# Sheet1.net
KiCad netlist of a schematic drawn in Altium Designer
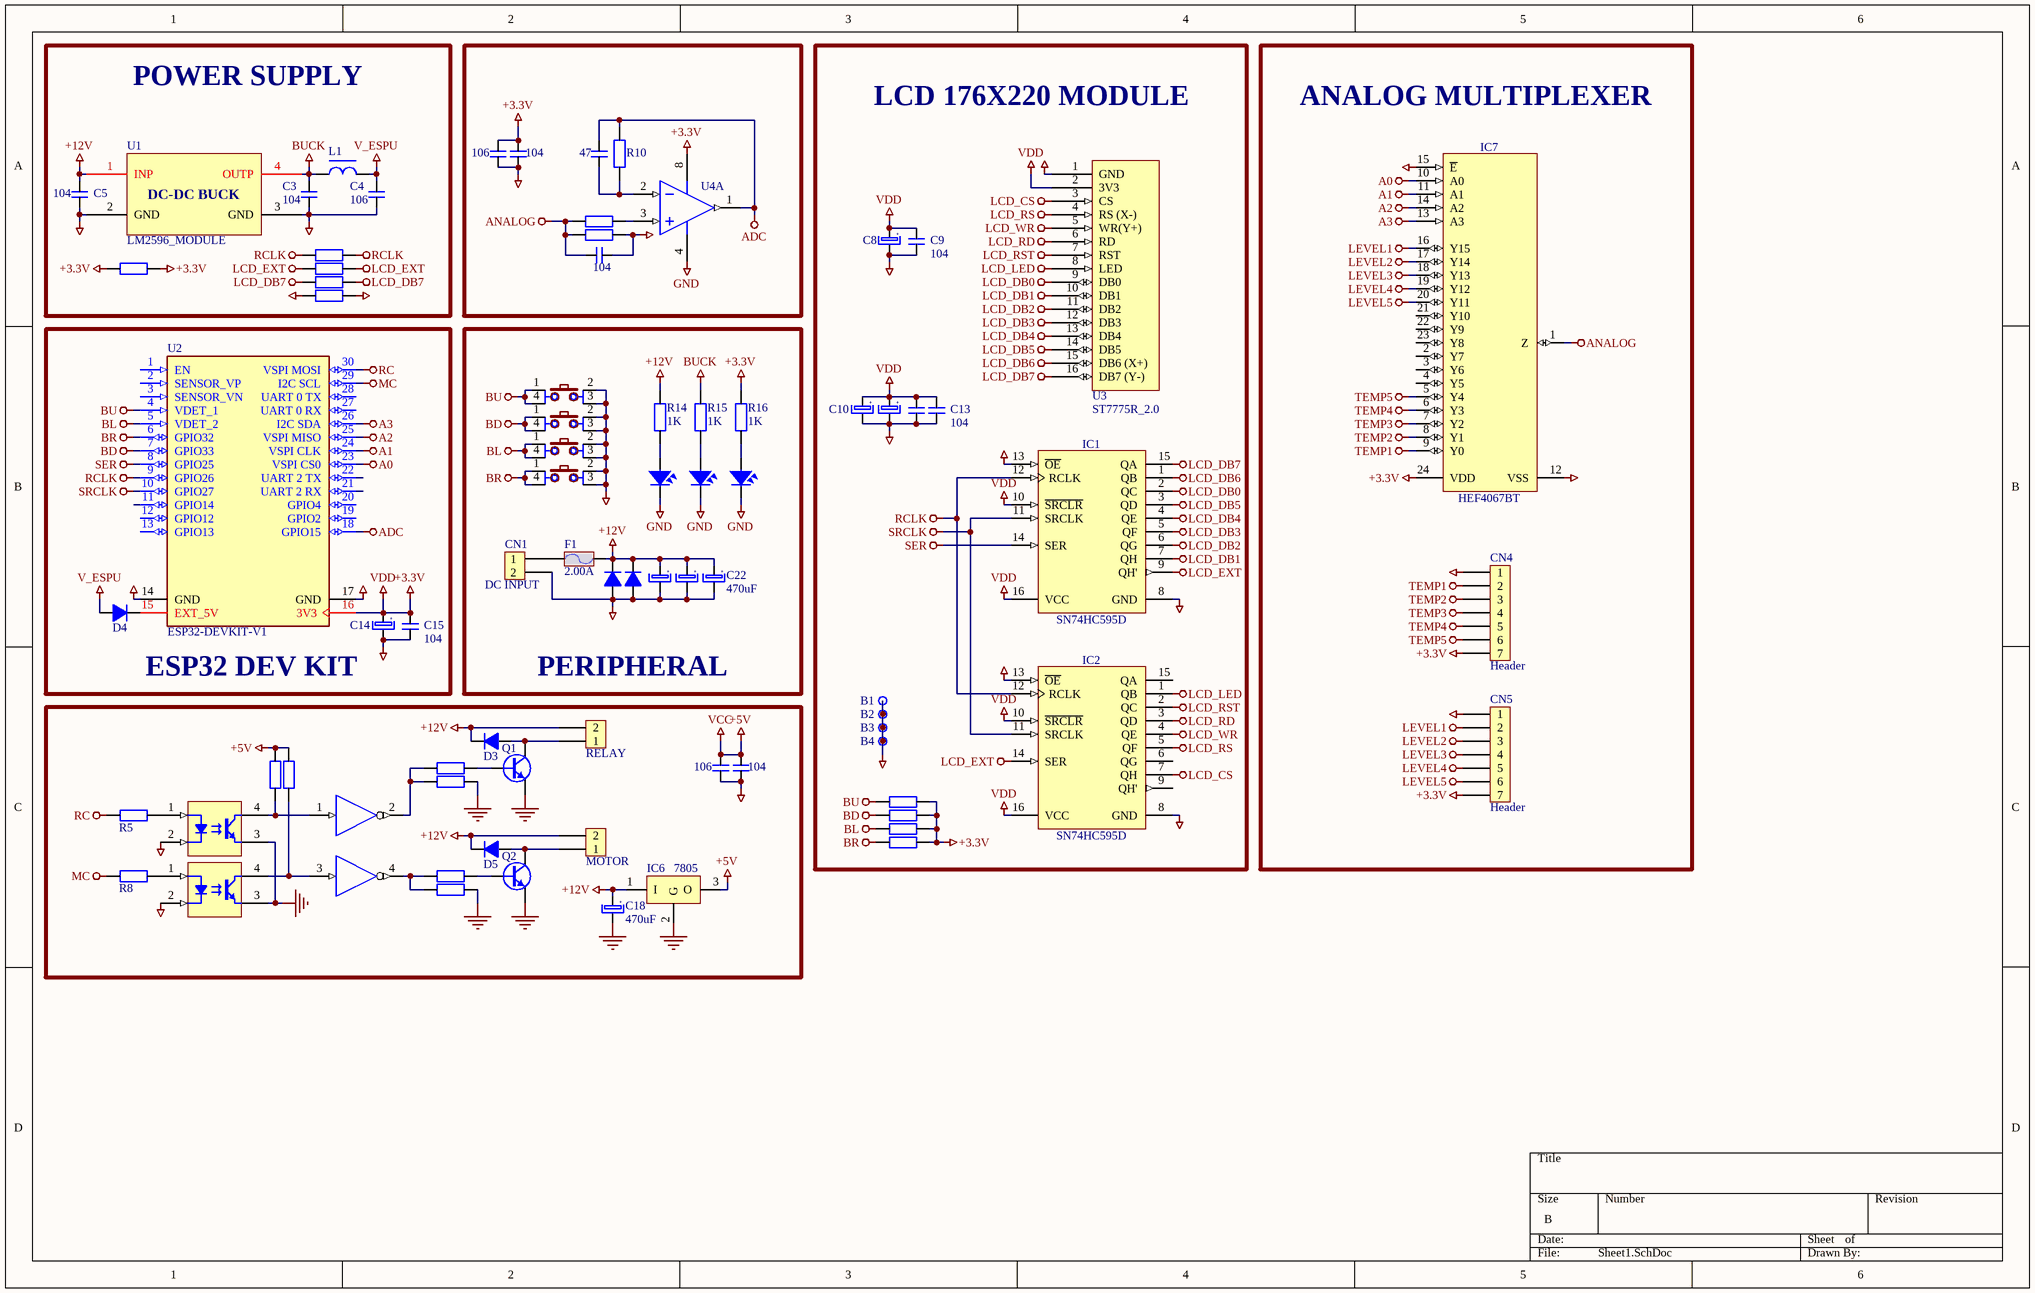
[diagram p0: Sheet1.SchDoc]

(export (version "E")
  (design (tool "Eeschema 10.0.6"))
  (components
    (comp (ref "B1")
      (value "Plated Hole")
      (footprint "MTG300_600")
      (description "Single Terminal Socket")
      (fields (field (name "PART NUMBER") "PLATED_HOLE3.0_PAD6.0") (field (name "AUTHOR") "CERN DEM JLC"))
      (libsource (lib "Eletro-mechanical") (part "Single Terminal Socket"))
    )
    (comp (ref "B2")
      (value "Plated Hole")
      (footprint "MTG300_600")
      (description "Single Terminal Socket")
      (fields (field (name "PART NUMBER") "PLATED_HOLE3.0_PAD6.0") (field (name "AUTHOR") "CERN DEM JLC"))
      (libsource (lib "Eletro-mechanical") (part "Single Terminal Socket"))
    )
    (comp (ref "B3")
      (value "Plated Hole")
      (footprint "MTG300_600")
      (description "Single Terminal Socket")
      (fields (field (name "PART NUMBER") "PLATED_HOLE3.0_PAD6.0") (field (name "AUTHOR") "CERN DEM JLC"))
      (libsource (lib "Eletro-mechanical") (part "Single Terminal Socket"))
    )
    (comp (ref "B4")
      (value "Plated Hole")
      (footprint "MTG300_600")
      (description "Single Terminal Socket")
      (fields (field (name "PART NUMBER") "PLATED_HOLE3.0_PAD6.0") (field (name "AUTHOR") "CERN DEM JLC"))
      (libsource (lib "Eletro-mechanical") (part "Single Terminal Socket"))
    )
    (comp (ref "C1")
      (value "106")
      (footprint "CAP-SMD-0805")
      (description "Non-polar capacitor")
      (libsource (lib "Library") (part "Cap-Non-SMD"))
    )
    (comp (ref "C2")
      (value "104")
      (footprint "CAP-SMD-0805")
      (description "Non-polar capacitor")
      (libsource (lib "Library") (part "Cap-Non-SMD"))
    )
    (comp (ref "C3")
      (value "104")
      (footprint "Cap-Non-150mil")
      (description "Non-polar capacitor")
      (libsource (lib "Library") (part "Cap-Non-Dip"))
    )
    (comp (ref "C4")
      (value "106")
      (footprint "CAP-SMD-0805")
      (description "Non-polar capacitor")
      (libsource (lib "Library") (part "Cap-Non-SMD"))
    )
    (comp (ref "C5")
      (value "104")
      (footprint "Cap-Non-150mil")
      (description "Non-polar capacitor")
      (libsource (lib "Library") (part "Cap-Non-Dip"))
    )
    (comp (ref "C6")
      (value "47")
      (footprint "CAP-SMD-0805")
      (description "Non-polar capacitor")
      (libsource (lib "Library") (part "Cap-Non-SMD"))
    )
    (comp (ref "C7")
      (value "104")
      (footprint "CAP-SMD-0805")
      (description "Non-polar capacitor")
      (libsource (lib "Library") (part "Cap-Non-SMD"))
    )
    (comp (ref "C8")
      (value "220uF")
      (footprint "Cap-P-2.5/5")
      (description "Polarized capacitor")
      (libsource (lib "Library") (part "Cap-Pol-Dip"))
    )
    (comp (ref "C9")
      (value "104")
      (footprint "Cap-Non-150mil")
      (description "Non-polar capacitor")
      (libsource (lib "Library") (part "Cap-Non-Dip"))
    )
    (comp (ref "C10")
      (value "220uF")
      (footprint "Cap-P-2.5/5")
      (description "Polarized capacitor")
      (libsource (lib "Library") (part "Cap-Pol-Dip"))
    )
    (comp (ref "C11")
      (value "220uF")
      (footprint "Cap-P-2.5/5")
      (description "Polarized capacitor")
      (libsource (lib "Library") (part "Cap-Pol-Dip"))
    )
    (comp (ref "C12")
      (value "104")
      (footprint "Cap-Non-150mil")
      (description "Non-polar capacitor")
      (libsource (lib "Library") (part "Cap-Non-Dip"))
    )
    (comp (ref "C13")
      (value "104")
      (footprint "Cap-Non-150mil")
      (description "Non-polar capacitor")
      (libsource (lib "Library") (part "Cap-Non-Dip"))
    )
    (comp (ref "C14")
      (value "220uF")
      (footprint "Cap-P-2.5/5")
      (description "Polarized capacitor")
      (libsource (lib "Library") (part "Cap-Pol-Dip"))
    )
    (comp (ref "C15")
      (value "104")
      (footprint "Cap-Non-150mil")
      (description "Non-polar capacitor")
      (libsource (lib "Library") (part "Cap-Non-Dip"))
    )
    (comp (ref "C16")
      (value "106")
      (footprint "CAP-SMD-0805")
      (description "Non-polar capacitor")
      (libsource (lib "Library") (part "Cap-Non-SMD"))
    )
    (comp (ref "C17")
      (value "104")
      (footprint "CAP-SMD-0805")
      (description "Non-polar capacitor")
      (libsource (lib "Library") (part "Cap-Non-SMD"))
    )
    (comp (ref "C18")
      (value "470uF")
      (footprint "Cap-P-3.8/6.3")
      (description "Polarized capacitor")
      (libsource (lib "Library") (part "Cap-Pol-Dip"))
    )
    (comp (ref "C20")
      (value "470uF")
      (footprint "Cap-P-3.8/6.3")
      (description "Polarized capacitor")
      (libsource (lib "Library") (part "Cap-Pol-Dip"))
    )
    (comp (ref "C21")
      (value "470uF")
      (footprint "Cap-P-3.8/6.3")
      (description "Polarized capacitor")
      (libsource (lib "Library") (part "Cap-Pol-Dip"))
    )
    (comp (ref "C22")
      (value "470uF")
      (footprint "Cap-P-3.8/6.3")
      (description "Polarized capacitor")
      (libsource (lib "Library") (part "Cap-Pol-Dip"))
    )
    (comp (ref "CN1") (value "DC INPUT") (footprint "KF2/5.08") (libsource (lib "Library") (part "KF 2")))
    (comp (ref "CN2") (value "RELAY") (footprint "KF2/5.08") (libsource (lib "") (part "KF 2_1")))
    (comp (ref "CN3") (value "MOTOR") (footprint "KF2/5.08") (libsource (lib "") (part "KF 2_1")))
    (comp (ref "CN4") (value "Header") (footprint "Header 7P") (libsource (lib "Library") (part "Header 7")))
    (comp (ref "CN5") (value "Header") (footprint "Header 7P") (libsource (lib "Library") (part "Header 7")))
    (comp (ref "D1")
      (value "SS14")
      (footprint "SOD 106")
      (description "Diode SMD")
      (libsource (lib "Library") (part "Diode SMD"))
    )
    (comp (ref "D2")
      (value "SS14")
      (footprint "SOD 106")
      (description "Diode SMD")
      (libsource (lib "Library") (part "Diode SMD"))
    )
    (comp (ref "D3")
      (value "SS14")
      (footprint "SOD 106")
      (description "Diode SMD")
      (libsource (lib "Library") (part "Diode SMD"))
    )
    (comp (ref "D4")
      (value "SS14")
      (footprint "SOD 106")
      (description "Diode SMD")
      (libsource (lib "Library") (part "Diode SMD"))
    )
    (comp (ref "D5")
      (value "SS14")
      (footprint "SOD 106")
      (description "Diode SMD")
      (libsource (lib "Library") (part "Diode SMD"))
    )
    (comp (ref "F1") (value "2.00A") (footprint "Fuse-Dip1") (libsource (lib "Library") (part "Fuse Dip")))
    (comp (ref "IC1")
      (value "SN74HC595D")
      (footprint "SOIC127P600X175-16N")
      (description "8-Bit Shift Register With 3-State Output Register")
      (fields (field (name "MANUFACTURER") "TEXAS INSTRUMENTS") (field (name "AUTHOR") "CERN DEM JLC"))
      (libsource (lib "ICs And Semiconductors") (part "74595"))
    )
    (comp (ref "IC2")
      (value "SN74HC595D")
      (footprint "SOIC127P600X175-16N")
      (description "8-Bit Shift Register With 3-State Output Register")
      (fields (field (name "MANUFACTURER") "TEXAS INSTRUMENTS") (field (name "AUTHOR") "CERN DEM JLC"))
      (libsource (lib "ICs And Semiconductors") (part "74595"))
    )
    (comp (ref "IC3")
      (value "FOD817DSD")
      (footprint "DIP4")
      (description "Single Optocoupler")
      (fields (field (name "MANUFACTURER") "FAIRCHILD SEMICONDUCTOR") (field (name "AUTHOR") "CERN DEM JLC"))
      (libsource (lib "ICs And Semiconductors") (part "Optocoupler Type7"))
    )
    (comp (ref "IC4")
      (value "74HC14D")
      (footprint "SOIC127P600X175-14N")
      (description "Hex Schmitt-Trigger Inverter")
      (fields (field (name "MANUFACTURER") "NXP SEMICONDUCTORS") (field (name "AUTHOR") "CERN DEM JLC"))
      (libsource (lib "ICs And Semiconductors") (part "7414"))
    )
    (comp (ref "IC5")
      (value "FOD817DSD")
      (footprint "DIP4")
      (description "Single Optocoupler")
      (fields (field (name "MANUFACTURER") "FAIRCHILD SEMICONDUCTOR") (field (name "AUTHOR") "CERN DEM JLC"))
      (libsource (lib "ICs And Semiconductors") (part "Optocoupler Type7"))
    )
    (comp (ref "IC6")
      (value "7805")
      (footprint "TO252")
      (description "Power IC, 5V-1A")
      (libsource (lib "Library") (part "7805"))
    )
    (comp (ref "IC7")
      (value "HEF4067BT")
      (footprint "SOIC127P1032X265-24N")
      (description "16-Channel Analog Multiplexer/Demultiplexer")
      (fields (field (name "MANUFACTURER") "NXP SEMICONDUCTORS") (field (name "AUTHOR") "CERN DEM JLC"))
      (libsource (lib "ICs And Semiconductors") (part "4067"))
    )
    (comp (ref "L1")
      (value "470uH")
      (footprint "L-DIP-M-5.3")
      (description "Inductor")
      (libsource (lib "Library") (part "IND-DIP-1"))
    )
    (comp (ref "LED1") (value "POWER") (footprint "LED-0805") (libsource (lib "Library") (part "LED_SMD")))
    (comp (ref "LED2") (value "ESP-5.0V") (footprint "LED-0805") (libsource (lib "Library") (part "LED_SMD")))
    (comp (ref "LED3") (value "ESP-3.3V") (footprint "LED-0805") (libsource (lib "Library") (part "LED_SMD")))
    (comp (ref "Q1")
      (value "MJD122G")
      (footprint "TO228P991X239-3N-R552X520")
      (description "NPN Transistor")
      (fields
        (field (name "PART NUMBER") "MJD340G")
        (field (name "MANUFACTURER") "ON SEMICONDUCTOR")
        (field (name "AUTHOR") "CERN DEM JLC")
      )
      (libsource (lib "ICs And Semiconductors") (part "NPN B1 E2 C3"))
    )
    (comp (ref "Q2")
      (value "MJD122G")
      (footprint "TO228P991X239-3N-R552X520")
      (description "NPN Transistor")
      (fields
        (field (name "PART NUMBER") "MJD340G")
        (field (name "MANUFACTURER") "ON SEMICONDUCTOR")
        (field (name "AUTHOR") "CERN DEM JLC")
      )
      (libsource (lib "ICs And Semiconductors") (part "NPN B1 E2 C3"))
    )
    (comp (ref "R1")
      (value "1K")
      (footprint "RES-SMD-0805")
      (description "Resistor 1/4W")
      (libsource (lib "Library") (part "Res 1/4W"))
    )
    (comp (ref "R2")
      (value "1K")
      (footprint "RES-SMD-0805")
      (description "Resistor 1/4W")
      (libsource (lib "Library") (part "Res 1/4W"))
    )
    (comp (ref "R3")
      (value "1K")
      (footprint "RES-SMD-0805")
      (description "Resistor 1/4W")
      (libsource (lib "Library") (part "Res 1/4W"))
    )
    (comp (ref "R4")
      (value "10K")
      (footprint "RES-SMD-0805")
      (description "Resistor 1/4W")
      (libsource (lib "Library") (part "Res 1/4W"))
    )
    (comp (ref "R5")
      (value "1K")
      (footprint "RES-SMD-0805")
      (description "Resistor 1/4W")
      (libsource (lib "Library") (part "Res 1/4W"))
    )
    (comp (ref "R6")
      (value "1K")
      (footprint "RES-SMD-0805")
      (description "Resistor 1/4W")
      (libsource (lib "Library") (part "Res 1/4W"))
    )
    (comp (ref "R7")
      (value "10K")
      (footprint "RES-SMD-0805")
      (description "Resistor 1/4W")
      (libsource (lib "Library") (part "Res 1/4W"))
    )
    (comp (ref "R8")
      (value "1K")
      (footprint "RES-SMD-0805")
      (description "Resistor 1/4W")
      (libsource (lib "Library") (part "Res 1/4W"))
    )
    (comp (ref "R10")
      (value "10K")
      (footprint "RES-SMD-0805")
      (description "Resistor SMD")
      (libsource (lib "Library") (part "Res SMD"))
    )
    (comp (ref "R11")
      (value "10K")
      (footprint "RES-SMD-0805")
      (description "Resistor SMD")
      (libsource (lib "Library") (part "Res SMD"))
    )
    (comp (ref "R12")
      (value "1K")
      (footprint "RES-SMD-0805")
      (description "Resistor SMD")
      (libsource (lib "Library") (part "Res SMD"))
    )
    (comp (ref "R13")
      (value "1K")
      (footprint "RES-SMD-0805")
      (description "Resistor 1/4W")
      (libsource (lib "Library") (part "Res 1/4W"))
    )
    (comp (ref "R14")
      (value "1K")
      (footprint "RES-SMD-0805")
      (description "Resistor 1/4W")
      (libsource (lib "Library") (part "Res 1/4W"))
    )
    (comp (ref "R15")
      (value "1K")
      (footprint "RES-SMD-0805")
      (description "Resistor 1/4W")
      (libsource (lib "Library") (part "Res 1/4W"))
    )
    (comp (ref "R16")
      (value "1K")
      (footprint "RES-SMD-0805")
      (description "Resistor 1/4W")
      (libsource (lib "Library") (part "Res 1/4W"))
    )
    (comp (ref "R17")
      (value "0R")
      (footprint "RES-SMD-0805")
      (description "Resistor SMD")
      (libsource (lib "Library") (part "Res SMD"))
    )
    (comp (ref "R18")
      (value "0R")
      (footprint "RES-SMD-0805")
      (description "Resistor SMD")
      (libsource (lib "Library") (part "Res SMD"))
    )
    (comp (ref "R19")
      (value "0R")
      (footprint "RES-SMD-0805")
      (description "Resistor SMD")
      (libsource (lib "Library") (part "Res SMD"))
    )
    (comp (ref "R20")
      (value "0R")
      (footprint "RES-SMD-1206")
      (description "Resistor SMD")
      (libsource (lib "Library") (part "Res SMD"))
    )
    (comp (ref "R21")
      (value "1K")
      (footprint "RES-SMD-0805")
      (description "Resistor 1/4W")
      (libsource (lib "Library") (part "Res 1/4W"))
    )
    (comp (ref "R22")
      (value "1K")
      (footprint "RES-SMD-0805")
      (description "Resistor 1/4W")
      (libsource (lib "Library") (part "Res 1/4W"))
    )
    (comp (ref "R23")
      (value "1K")
      (footprint "RES-SMD-0805")
      (description "Resistor 1/4W")
      (libsource (lib "Library") (part "Res 1/4W"))
    )
    (comp (ref "R27")
      (value "0R")
      (footprint "RES-SMD-1206")
      (description "Resistor 1/4W")
      (libsource (lib "Library") (part "Res 1/4W"))
    )
    (comp (ref "SW1")
      (value "UP")
      (footprint "Button-Dip4/6x6")
      (description "Switch button 4 pin")
      (libsource (lib "Library") (part "Button-4"))
    )
    (comp (ref "SW2")
      (value "DOWN")
      (footprint "Button-Dip4/6x6")
      (description "Switch button 4 pin")
      (libsource (lib "Library") (part "Button-4"))
    )
    (comp (ref "SW3")
      (value "LEFT")
      (footprint "Button-Dip4/6x6")
      (description "Switch button 4 pin")
      (libsource (lib "Library") (part "Button-4"))
    )
    (comp (ref "SW4")
      (value "RIGHT")
      (footprint "Button-Dip4/6x6")
      (description "Switch button 4 pin")
      (libsource (lib "Library") (part "Button-4"))
    )
    (comp (ref "U1")
      (value "LM2596_MODULE")
      (footprint "LM2596_MODULE")
      (libsource (lib "TOAN_VERSION_1_0") (part "LM2596_MODULE"))
    )
    (comp (ref "U2")
      (value "ESP32-DEVKIT-V1")
      (footprint "MODULE_ESP32-DEVKITC-32D")
      (fields (field (name "MF") "Espressif Systems") (field (name "MP") "ESP32-DEVKITC-32D"))
      (libsource (lib "TOAN_VERSION_1_0") (part "ESP32-DEVKIT-V1"))
    )
    (comp (ref "U3")
      (value "ST7775R_2.0")
      (footprint "LCD_176X220_MODULE")
      (libsource (lib "TOAN_VERSION_1_0") (part "LCD_176x220_ST7775R"))
    )
    (comp (ref "U4")
      (value "LM6132")
      (footprint "SOIC-8S")
      (description "Dual Low Power 10 MHz Rail-to-Rail I/O Operational Amplifier, 8-pin Narrow SOIC")
      (fields
        (field (name "PARTNUMBER") "LM6132AIM")
        (field (name "MANUFACTURER") "National Semiconductor")
        (field (name "PUBLISHER") "Altium Limited")
      )
      (libsource (lib "NSC Amplifier") (part "LM6132AIM"))
    )
  )
  (nets
    (net (code "1") (name "+3.3V") (class "Default")
      (node (ref "C1") (pin "2") (pinfunction "2_2") (pintype "passive"))
      (node (ref "C10") (pin "1") (pinfunction "1_1") (pintype "passive"))
      (node (ref "C11") (pin "1") (pinfunction "1_1") (pintype "passive"))
      (node (ref "C12") (pin "2") (pinfunction "2_2") (pintype "passive"))
      (node (ref "C13") (pin "2") (pinfunction "2_2") (pintype "passive"))
      (node (ref "C14") (pin "1") (pinfunction "1_1") (pintype "passive"))
      (node (ref "C15") (pin "2") (pinfunction "2_2") (pintype "passive"))
      (node (ref "C2") (pin "2") (pinfunction "2_2") (pintype "passive"))
      (node (ref "C8") (pin "1") (pinfunction "1_1") (pintype "passive"))
      (node (ref "C9") (pin "2") (pinfunction "2_2") (pintype "passive"))
      (node (ref "CN4") (pin "7") (pinfunction "7_7") (pintype "passive"))
      (node (ref "CN5") (pin "7") (pinfunction "7_7") (pintype "passive"))
      (node (ref "IC1") (pin "10") (pinfunction "~{SRCLR}_10") (pintype "input"))
      (node (ref "IC1") (pin "16") (pinfunction "VCC_16") (pintype "power_in"))
      (node (ref "IC2") (pin "10") (pinfunction "~{SRCLR}_10") (pintype "input"))
      (node (ref "IC2") (pin "16") (pinfunction "VCC_16") (pintype "power_in"))
      (node (ref "IC7") (pin "24") (pinfunction "VDD_24") (pintype "power_in"))
      (node (ref "R13") (pin "1") (pinfunction "1_1") (pintype "passive"))
      (node (ref "R16") (pin "2") (pinfunction "2_2") (pintype "passive"))
      (node (ref "R21") (pin "1") (pinfunction "1_1") (pintype "passive"))
      (node (ref "R22") (pin "1") (pinfunction "1_1") (pintype "passive"))
      (node (ref "R23") (pin "1") (pinfunction "1_1") (pintype "passive"))
      (node (ref "R27") (pin "1") (pinfunction "1_1") (pintype "passive"))
      (node (ref "R27") (pin "2") (pinfunction "2_2") (pintype "passive"))
      (node (ref "U2") (pin "16") (pinfunction "3V3_16") (pintype "power_in"))
      (node (ref "U3") (pin "2") (pinfunction "3V3_2") (pintype "power_in"))
      (node (ref "U4") (pin "8") (pinfunction "V+_8") (pintype "power_in"))
    )
    (net (code "2") (name "+5V") (class "Default")
      (node (ref "C16") (pin "2") (pinfunction "2_2") (pintype "passive"))
      (node (ref "C17") (pin "2") (pinfunction "2_2") (pintype "passive"))
      (node (ref "IC4") (pin "14") (pinfunction "VCC_14") (pintype "power_in"))
      (node (ref "IC6") (pin "3") (pinfunction "O_3") (pintype "passive"))
      (node (ref "R2") (pin "2") (pinfunction "2_2") (pintype "passive"))
      (node (ref "R3") (pin "2") (pinfunction "2_2") (pintype "passive"))
    )
    (net (code "3") (name "+12V") (class "Default")
      (node (ref "C18") (pin "1") (pinfunction "1_1") (pintype "passive"))
      (node (ref "C20") (pin "1") (pinfunction "1_1") (pintype "passive"))
      (node (ref "C21") (pin "1") (pinfunction "1_1") (pintype "passive"))
      (node (ref "C22") (pin "1") (pinfunction "1_1") (pintype "passive"))
      (node (ref "C5") (pin "1") (pinfunction "1_1") (pintype "passive"))
      (node (ref "CN2") (pin "2") (pinfunction "2_2") (pintype "passive"))
      (node (ref "CN3") (pin "2") (pinfunction "2_2") (pintype "passive"))
      (node (ref "D1") (pin "2") (pinfunction "K_2") (pintype "passive"))
      (node (ref "D2") (pin "2") (pinfunction "K_2") (pintype "passive"))
      (node (ref "D3") (pin "2") (pinfunction "K_2") (pintype "passive"))
      (node (ref "D5") (pin "2") (pinfunction "K_2") (pintype "passive"))
      (node (ref "F1") (pin "2") (pinfunction "2_2") (pintype "passive"))
      (node (ref "IC6") (pin "1") (pinfunction "I_1") (pintype "passive"))
      (node (ref "R14") (pin "2") (pinfunction "2_2") (pintype "passive"))
      (node (ref "U1") (pin "1") (pinfunction "INP_1") (pintype "power_in"))
    )
    (net (code "4") (name "A0") (class "Default")
      (node (ref "IC7") (pin "10") (pinfunction "A0_10") (pintype "input"))
      (node (ref "U2") (pin "23") (pinfunction "VSPI_CS0_23") (pintype "bidirectional"))
    )
    (net (code "5") (name "A1") (class "Default")
      (node (ref "IC7") (pin "11") (pinfunction "A1_11") (pintype "input"))
      (node (ref "U2") (pin "24") (pinfunction "VSPI_CLK_24") (pintype "bidirectional"))
    )
    (net (code "6") (name "A2") (class "Default")
      (node (ref "IC7") (pin "14") (pinfunction "A2_14") (pintype "input"))
      (node (ref "U2") (pin "25") (pinfunction "VSPI_MISO_25") (pintype "bidirectional"))
    )
    (net (code "7") (name "A3") (class "Default")
      (node (ref "IC7") (pin "13") (pinfunction "A3_13") (pintype "input"))
      (node (ref "U2") (pin "26") (pinfunction "I2C_SDA_26") (pintype "bidirectional"))
    )
    (net (code "8") (name "ADC") (class "Default")
      (node (ref "C6") (pin "2") (pinfunction "2_2") (pintype "passive"))
      (node (ref "R10") (pin "2") (pinfunction "2_2") (pintype "passive"))
      (node (ref "U2") (pin "18") (pinfunction "GPIO15_18") (pintype "bidirectional"))
      (node (ref "U4") (pin "1") (pinfunction "OUTA_1") (pintype "output"))
    )
    (net (code "9") (name "ANALOG") (class "Default")
      (node (ref "C7") (pin "1") (pinfunction "1_1") (pintype "passive"))
      (node (ref "IC7") (pin "1") (pinfunction "Z_1") (pintype "bidirectional"))
      (node (ref "R11") (pin "1") (pinfunction "1_1") (pintype "passive"))
      (node (ref "R12") (pin "1") (pinfunction "1_1") (pintype "passive"))
    )
    (net (code "10") (name "BD") (class "Default")
      (node (ref "R13") (pin "2") (pinfunction "2_2") (pintype "passive"))
      (node (ref "SW2") (pin "1") (pintype "passive"))
      (node (ref "SW2") (pin "4") (pinfunction "4_4") (pintype "passive"))
      (node (ref "U2") (pin "7") (pinfunction "GPIO33_7") (pintype "bidirectional"))
    )
    (net (code "11") (name "BL") (class "Default")
      (node (ref "R22") (pin "2") (pinfunction "2_2") (pintype "passive"))
      (node (ref "SW3") (pin "1") (pintype "passive"))
      (node (ref "SW3") (pin "4") (pinfunction "4_4") (pintype "passive"))
      (node (ref "U2") (pin "5") (pinfunction "VDET_2_5") (pintype "input"))
    )
    (net (code "12") (name "BR") (class "Default")
      (node (ref "R21") (pin "2") (pinfunction "2_2") (pintype "passive"))
      (node (ref "SW4") (pin "1") (pintype "passive"))
      (node (ref "SW4") (pin "4") (pinfunction "4_4") (pintype "passive"))
      (node (ref "U2") (pin "6") (pinfunction "GPIO32_6") (pintype "bidirectional"))
    )
    (net (code "13") (name "BU") (class "Default")
      (node (ref "R23") (pin "2") (pinfunction "2_2") (pintype "passive"))
      (node (ref "SW1") (pin "1") (pintype "passive"))
      (node (ref "SW1") (pin "4") (pinfunction "4_4") (pintype "passive"))
      (node (ref "U2") (pin "4") (pinfunction "VDET_1_4") (pintype "input"))
    )
    (net (code "14") (name "BUCK") (class "Default")
      (node (ref "C3") (pin "1") (pinfunction "1_1") (pintype "passive"))
      (node (ref "L1") (pin "1") (pinfunction "1_1") (pintype "passive"))
      (node (ref "R15") (pin "2") (pinfunction "2_2") (pintype "passive"))
      (node (ref "U1") (pin "4") (pinfunction "OUTP_4") (pintype "power_in"))
    )
    (net (code "15") (name "GND") (class "Default")
      (node (ref "B1") (pin "1") (pinfunction "1_1") (pintype "bidirectional"))
      (node (ref "B2") (pin "1") (pinfunction "1_1") (pintype "bidirectional"))
      (node (ref "B3") (pin "1") (pinfunction "1_1") (pintype "bidirectional"))
      (node (ref "B4") (pin "1") (pinfunction "1_1") (pintype "bidirectional"))
      (node (ref "C1") (pin "1") (pinfunction "1_1") (pintype "passive"))
      (node (ref "C10") (pin "2") (pinfunction "2_2") (pintype "passive"))
      (node (ref "C11") (pin "2") (pinfunction "2_2") (pintype "passive"))
      (node (ref "C12") (pin "1") (pinfunction "1_1") (pintype "passive"))
      (node (ref "C13") (pin "1") (pinfunction "1_1") (pintype "passive"))
      (node (ref "C14") (pin "2") (pinfunction "2_2") (pintype "passive"))
      (node (ref "C15") (pin "1") (pinfunction "1_1") (pintype "passive"))
      (node (ref "C16") (pin "1") (pinfunction "1_1") (pintype "passive"))
      (node (ref "C17") (pin "1") (pinfunction "1_1") (pintype "passive"))
      (node (ref "C18") (pin "2") (pinfunction "2_2") (pintype "passive"))
      (node (ref "C2") (pin "1") (pinfunction "1_1") (pintype "passive"))
      (node (ref "C20") (pin "2") (pinfunction "2_2") (pintype "passive"))
      (node (ref "C21") (pin "2") (pinfunction "2_2") (pintype "passive"))
      (node (ref "C22") (pin "2") (pinfunction "2_2") (pintype "passive"))
      (node (ref "C3") (pin "2") (pinfunction "2_2") (pintype "passive"))
      (node (ref "C4") (pin "1") (pinfunction "1_1") (pintype "passive"))
      (node (ref "C5") (pin "2") (pinfunction "2_2") (pintype "passive"))
      (node (ref "C7") (pin "2") (pinfunction "2_2") (pintype "passive"))
      (node (ref "C8") (pin "2") (pinfunction "2_2") (pintype "passive"))
      (node (ref "C9") (pin "1") (pinfunction "1_1") (pintype "passive"))
      (node (ref "CN1") (pin "2") (pinfunction "2_2") (pintype "passive"))
      (node (ref "CN4") (pin "1") (pinfunction "1_1") (pintype "passive"))
      (node (ref "CN5") (pin "1") (pinfunction "1_1") (pintype "passive"))
      (node (ref "D1") (pin "1") (pinfunction "A_1") (pintype "passive"))
      (node (ref "D2") (pin "1") (pinfunction "A_1") (pintype "passive"))
      (node (ref "IC1") (pin "13") (pinfunction "~{OE}_13") (pintype "input"))
      (node (ref "IC1") (pin "8") (pinfunction "GND_8") (pintype "power_in"))
      (node (ref "IC2") (pin "13") (pinfunction "~{OE}_13") (pintype "input"))
      (node (ref "IC2") (pin "8") (pinfunction "GND_8") (pintype "power_in"))
      (node (ref "IC3") (pin "2") (pinfunction "C_2") (pintype "input"))
      (node (ref "IC3") (pin "3") (pinfunction "E_3") (pintype "open_emitter"))
      (node (ref "IC4") (pin "7") (pinfunction "GND_7") (pintype "power_in"))
      (node (ref "IC5") (pin "2") (pinfunction "C_2") (pintype "input"))
      (node (ref "IC5") (pin "3") (pinfunction "E_3") (pintype "open_emitter"))
      (node (ref "IC6") (pin "2") (pinfunction "G_2") (pintype "passive"))
      (node (ref "IC7") (pin "12") (pinfunction "VSS_12") (pintype "power_in"))
      (node (ref "IC7") (pin "15") (pinfunction "~{E}_15") (pintype "input"))
      (node (ref "LED1") (pin "2") (pinfunction "2_2") (pintype "passive"))
      (node (ref "LED2") (pin "2") (pinfunction "2_2") (pintype "passive"))
      (node (ref "LED3") (pin "2") (pinfunction "2_2") (pintype "passive"))
      (node (ref "Q1") (pin "2") (pinfunction "E_2") (pintype "passive"))
      (node (ref "Q2") (pin "2") (pinfunction "E_2") (pintype "passive"))
      (node (ref "R12") (pin "2") (pinfunction "2_2") (pintype "passive"))
      (node (ref "R20") (pin "1") (pinfunction "1_1") (pintype "passive"))
      (node (ref "R20") (pin "2") (pinfunction "2_2") (pintype "passive"))
      (node (ref "R4") (pin "1") (pinfunction "1_1") (pintype "passive"))
      (node (ref "R7") (pin "1") (pinfunction "1_1") (pintype "passive"))
      (node (ref "SW1") (pin "2") (pinfunction "2_2") (pintype "passive"))
      (node (ref "SW1") (pin "3") (pinfunction "3_3") (pintype "passive"))
      (node (ref "SW2") (pin "2") (pinfunction "2_2") (pintype "passive"))
      (node (ref "SW2") (pin "3") (pinfunction "3_3") (pintype "passive"))
      (node (ref "SW3") (pin "2") (pinfunction "2_2") (pintype "passive"))
      (node (ref "SW3") (pin "3") (pinfunction "3_3") (pintype "passive"))
      (node (ref "SW4") (pin "2") (pinfunction "2_2") (pintype "passive"))
      (node (ref "SW4") (pin "3") (pinfunction "3_3") (pintype "passive"))
      (node (ref "U1") (pin "2") (pinfunction "GND_2") (pintype "power_in"))
      (node (ref "U1") (pin "3") (pinfunction "GND_3") (pintype "power_in"))
      (node (ref "U2") (pin "14") (pinfunction "GND_14") (pintype "power_in"))
      (node (ref "U2") (pin "17") (pinfunction "GND_17") (pintype "power_in"))
      (node (ref "U3") (pin "1") (pinfunction "GND_1") (pintype "power_in"))
      (node (ref "U4") (pin "4") (pinfunction "V-_4") (pintype "power_in"))
    )
    (net (code "16") (name "LCD_CS") (class "Default")
      (node (ref "IC2") (pin "7") (pinfunction "QH_7") (pintype "tri_state"))
      (node (ref "U3") (pin "3") (pinfunction "CS_3") (pintype "input"))
    )
    (net (code "17") (name "LCD_DB0") (class "Default")
      (node (ref "IC1") (pin "2") (pinfunction "QC_2") (pintype "tri_state"))
      (node (ref "U3") (pin "9") (pinfunction "DB0_9") (pintype "bidirectional"))
    )
    (net (code "18") (name "LCD_DB1") (class "Default")
      (node (ref "IC1") (pin "7") (pinfunction "QH_7") (pintype "tri_state"))
      (node (ref "U3") (pin "10") (pinfunction "DB1_10") (pintype "bidirectional"))
    )
    (net (code "19") (name "LCD_DB2") (class "Default")
      (node (ref "IC1") (pin "6") (pinfunction "QG_6") (pintype "tri_state"))
      (node (ref "U3") (pin "11") (pinfunction "DB2_11") (pintype "bidirectional"))
    )
    (net (code "20") (name "LCD_DB3") (class "Default")
      (node (ref "IC1") (pin "5") (pinfunction "QF_5") (pintype "tri_state"))
      (node (ref "U3") (pin "12") (pinfunction "DB3_12") (pintype "bidirectional"))
    )
    (net (code "21") (name "LCD_DB4") (class "Default")
      (node (ref "IC1") (pin "4") (pinfunction "QE_4") (pintype "tri_state"))
      (node (ref "U3") (pin "13") (pinfunction "DB4_13") (pintype "bidirectional"))
    )
    (net (code "22") (name "LCD_DB5") (class "Default")
      (node (ref "IC1") (pin "3") (pinfunction "QD_3") (pintype "tri_state"))
      (node (ref "U3") (pin "14") (pinfunction "DB5_14") (pintype "bidirectional"))
    )
    (net (code "23") (name "LCD_DB6") (class "Default")
      (node (ref "IC1") (pin "1") (pinfunction "QB_1") (pintype "tri_state"))
      (node (ref "U3") (pin "15") (pinfunction "DB6_(X+)_15") (pintype "bidirectional"))
    )
    (net (code "24") (name "LCD_DB7") (class "Default")
      (node (ref "IC1") (pin "15") (pinfunction "QA_15") (pintype "tri_state"))
      (node (ref "R18") (pin "1") (pinfunction "1_1") (pintype "passive"))
      (node (ref "R18") (pin "2") (pinfunction "2_2") (pintype "passive"))
      (node (ref "U3") (pin "16") (pinfunction "DB7_(Y-)_16") (pintype "bidirectional"))
    )
    (net (code "25") (name "LCD_EXT") (class "Default")
      (node (ref "IC1") (pin "9") (pinfunction "QH'_9") (pintype "output"))
      (node (ref "IC2") (pin "14") (pinfunction "SER_14") (pintype "input"))
      (node (ref "R19") (pin "1") (pinfunction "1_1") (pintype "passive"))
      (node (ref "R19") (pin "2") (pinfunction "2_2") (pintype "passive"))
    )
    (net (code "26") (name "LCD_LED") (class "Default")
      (node (ref "IC2") (pin "1") (pinfunction "QB_1") (pintype "tri_state"))
      (node (ref "U3") (pin "8") (pinfunction "LED_8") (pintype "input"))
    )
    (net (code "27") (name "LCD_RD") (class "Default")
      (node (ref "IC2") (pin "3") (pinfunction "QD_3") (pintype "tri_state"))
      (node (ref "U3") (pin "6") (pinfunction "RD_6") (pintype "input"))
    )
    (net (code "28") (name "LCD_RS") (class "Default")
      (node (ref "IC2") (pin "5") (pinfunction "QF_5") (pintype "tri_state"))
      (node (ref "U3") (pin "4") (pinfunction "RS_(X-)_4") (pintype "input"))
    )
    (net (code "29") (name "LCD_RST") (class "Default")
      (node (ref "IC2") (pin "2") (pinfunction "QC_2") (pintype "tri_state"))
      (node (ref "U3") (pin "7") (pinfunction "RST_7") (pintype "input"))
    )
    (net (code "30") (name "LCD_WR") (class "Default")
      (node (ref "IC2") (pin "4") (pinfunction "QE_4") (pintype "tri_state"))
      (node (ref "U3") (pin "5") (pinfunction "WR(Y+)_5") (pintype "input"))
    )
    (net (code "31") (name "LEVEL1") (class "Default")
      (node (ref "CN5") (pin "2") (pinfunction "2_2") (pintype "passive"))
      (node (ref "IC7") (pin "16") (pinfunction "Y15_16") (pintype "bidirectional"))
    )
    (net (code "32") (name "LEVEL2") (class "Default")
      (node (ref "CN5") (pin "3") (pinfunction "3_3") (pintype "passive"))
      (node (ref "IC7") (pin "17") (pinfunction "Y14_17") (pintype "bidirectional"))
    )
    (net (code "33") (name "LEVEL3") (class "Default")
      (node (ref "CN5") (pin "4") (pinfunction "4_4") (pintype "passive"))
      (node (ref "IC7") (pin "18") (pinfunction "Y13_18") (pintype "bidirectional"))
    )
    (net (code "34") (name "LEVEL4") (class "Default")
      (node (ref "CN5") (pin "5") (pinfunction "5_5") (pintype "passive"))
      (node (ref "IC7") (pin "19") (pinfunction "Y12_19") (pintype "bidirectional"))
    )
    (net (code "35") (name "LEVEL5") (class "Default")
      (node (ref "CN5") (pin "6") (pinfunction "6_6") (pintype "passive"))
      (node (ref "IC7") (pin "20") (pinfunction "Y11_20") (pintype "bidirectional"))
    )
    (net (code "36") (name "MC") (class "Default")
      (node (ref "R8") (pin "2") (pinfunction "2_2") (pintype "passive"))
      (node (ref "U2") (pin "29") (pinfunction "I2C_SCL_29") (pintype "bidirectional"))
    )
    (net (code "37") (name "Net-(CN1-Pad1)") (class "Default")
      (node (ref "CN1") (pin "1") (pinfunction "1_1") (pintype "passive"))
      (node (ref "F1") (pin "1") (pinfunction "1_1") (pintype "passive"))
    )
    (net (code "38") (name "Net-(D3-A)") (class "Default")
      (node (ref "CN2") (pin "1") (pinfunction "1_1") (pintype "passive"))
      (node (ref "D3") (pin "1") (pinfunction "A_1") (pintype "passive"))
      (node (ref "Q1") (pin "3") (pinfunction "C_3") (pintype "passive"))
    )
    (net (code "39") (name "Net-(D4-K)") (class "Default")
      (node (ref "D4") (pin "2") (pinfunction "K_2") (pintype "passive"))
      (node (ref "U2") (pin "15") (pinfunction "EXT_5V_15") (pintype "power_in"))
    )
    (net (code "40") (name "Net-(D5-A)") (class "Default")
      (node (ref "CN3") (pin "1") (pinfunction "1_1") (pintype "passive"))
      (node (ref "D5") (pin "1") (pinfunction "A_1") (pintype "passive"))
      (node (ref "Q2") (pin "3") (pinfunction "C_3") (pintype "passive"))
    )
    (net (code "41") (name "Net-(IC3-A)") (class "Default")
      (node (ref "IC3") (pin "1") (pinfunction "A_1") (pintype "input"))
      (node (ref "R5") (pin "1") (pinfunction "1_1") (pintype "passive"))
    )
    (net (code "42") (name "Net-(IC4A-IN)") (class "Default")
      (node (ref "IC3") (pin "4") (pinfunction "C_4") (pintype "open_collector"))
      (node (ref "IC4") (pin "1") (pinfunction "IN_1") (pintype "input"))
      (node (ref "R2") (pin "1") (pinfunction "1_1") (pintype "passive"))
    )
    (net (code "43") (name "Net-(IC4A-OUT)") (class "Default")
      (node (ref "IC4") (pin "2") (pinfunction "OUT_2") (pintype "output"))
      (node (ref "R1") (pin "1") (pinfunction "1_1") (pintype "passive"))
      (node (ref "R4") (pin "2") (pinfunction "2_2") (pintype "passive"))
    )
    (net (code "44") (name "Net-(IC4B-IN)") (class "Default")
      (node (ref "IC4") (pin "3") (pinfunction "IN_3") (pintype "input"))
      (node (ref "IC5") (pin "4") (pinfunction "C_4") (pintype "open_collector"))
      (node (ref "R3") (pin "1") (pinfunction "1_1") (pintype "passive"))
    )
    (net (code "45") (name "Net-(IC4B-OUT)") (class "Default")
      (node (ref "IC4") (pin "4") (pinfunction "OUT_4") (pintype "output"))
      (node (ref "R6") (pin "1") (pinfunction "1_1") (pintype "passive"))
      (node (ref "R7") (pin "2") (pinfunction "2_2") (pintype "passive"))
    )
    (net (code "46") (name "Net-(IC5-A)") (class "Default")
      (node (ref "IC5") (pin "1") (pinfunction "A_1") (pintype "input"))
      (node (ref "R8") (pin "1") (pinfunction "1_1") (pintype "passive"))
    )
    (net (code "47") (name "Net-(LED1-Pad1)") (class "Default")
      (node (ref "LED1") (pin "1") (pinfunction "1_1") (pintype "passive"))
      (node (ref "R14") (pin "1") (pinfunction "1_1") (pintype "passive"))
    )
    (net (code "48") (name "Net-(LED2-Pad1)") (class "Default")
      (node (ref "LED2") (pin "1") (pinfunction "1_1") (pintype "passive"))
      (node (ref "R15") (pin "1") (pinfunction "1_1") (pintype "passive"))
    )
    (net (code "49") (name "Net-(LED3-Pad1)") (class "Default")
      (node (ref "LED3") (pin "1") (pinfunction "1_1") (pintype "passive"))
      (node (ref "R16") (pin "1") (pinfunction "1_1") (pintype "passive"))
    )
    (net (code "50") (name "Net-(Q1-B)") (class "Default")
      (node (ref "Q1") (pin "1") (pinfunction "B_1") (pintype "passive"))
      (node (ref "R1") (pin "2") (pinfunction "2_2") (pintype "passive"))
    )
    (net (code "51") (name "Net-(Q2-B)") (class "Default")
      (node (ref "Q2") (pin "1") (pinfunction "B_1") (pintype "passive"))
      (node (ref "R6") (pin "2") (pinfunction "2_2") (pintype "passive"))
    )
    (net (code "52") (name "Net-(U4A-INA+)") (class "Default")
      (node (ref "R11") (pin "2") (pinfunction "2_2") (pintype "passive"))
      (node (ref "U4") (pin "3") (pinfunction "INA+_3") (pintype "input"))
    )
    (net (code "53") (name "Net-(U4A-INA-)") (class "Default")
      (node (ref "C6") (pin "1") (pinfunction "1_1") (pintype "passive"))
      (node (ref "R10") (pin "1") (pinfunction "1_1") (pintype "passive"))
      (node (ref "U4") (pin "2") (pinfunction "INA-_2") (pintype "input"))
    )
    (net (code "54") (name "RC") (class "Default")
      (node (ref "R5") (pin "2") (pinfunction "2_2") (pintype "passive"))
      (node (ref "U2") (pin "30") (pinfunction "VSPI_MOSI_30") (pintype "bidirectional"))
    )
    (net (code "55") (name "RCLK") (class "Default")
      (node (ref "IC1") (pin "12") (pinfunction "RCLK_12") (pintype "input"))
      (node (ref "IC2") (pin "12") (pinfunction "RCLK_12") (pintype "input"))
      (node (ref "R17") (pin "1") (pinfunction "1_1") (pintype "passive"))
      (node (ref "R17") (pin "2") (pinfunction "2_2") (pintype "passive"))
      (node (ref "U2") (pin "9") (pinfunction "GPIO26_9") (pintype "bidirectional"))
    )
    (net (code "56") (name "SER") (class "Default")
      (node (ref "IC1") (pin "14") (pinfunction "SER_14") (pintype "input"))
      (node (ref "U2") (pin "8") (pinfunction "GPIO25_8") (pintype "bidirectional"))
    )
    (net (code "57") (name "SRCLK") (class "Default")
      (node (ref "IC1") (pin "11") (pinfunction "SRCLK_11") (pintype "input"))
      (node (ref "IC2") (pin "11") (pinfunction "SRCLK_11") (pintype "input"))
      (node (ref "U2") (pin "10") (pinfunction "GPIO27_10") (pintype "bidirectional"))
    )
    (net (code "58") (name "TEMP1") (class "Default")
      (node (ref "CN4") (pin "2") (pinfunction "2_2") (pintype "passive"))
      (node (ref "IC7") (pin "9") (pinfunction "Y0_9") (pintype "bidirectional"))
    )
    (net (code "59") (name "TEMP2") (class "Default")
      (node (ref "CN4") (pin "3") (pinfunction "3_3") (pintype "passive"))
      (node (ref "IC7") (pin "8") (pinfunction "Y1_8") (pintype "bidirectional"))
    )
    (net (code "60") (name "TEMP3") (class "Default")
      (node (ref "CN4") (pin "4") (pinfunction "4_4") (pintype "passive"))
      (node (ref "IC7") (pin "7") (pinfunction "Y2_7") (pintype "bidirectional"))
    )
    (net (code "61") (name "TEMP4") (class "Default")
      (node (ref "CN4") (pin "5") (pinfunction "5_5") (pintype "passive"))
      (node (ref "IC7") (pin "6") (pinfunction "Y3_6") (pintype "bidirectional"))
    )
    (net (code "62") (name "TEMP5") (class "Default")
      (node (ref "CN4") (pin "6") (pinfunction "6_6") (pintype "passive"))
      (node (ref "IC7") (pin "5") (pinfunction "Y4_5") (pintype "bidirectional"))
    )
    (net (code "63") (name "V_ESPU") (class "Default")
      (node (ref "C4") (pin "2") (pinfunction "2_2") (pintype "passive"))
      (node (ref "D4") (pin "1") (pinfunction "A_1") (pintype "passive"))
      (node (ref "L1") (pin "2") (pinfunction "2_2") (pintype "passive"))
    )
    (net (code "64") (name "unconnected-(IC2-QA-Pad15)") (class "Default")
      (node (ref "IC2") (pin "15") (pinfunction "QA_15") (pintype "tri_state"))
    )
    (net (code "65") (name "unconnected-(IC2-QG-Pad6)") (class "Default")
      (node (ref "IC2") (pin "6") (pinfunction "QG_6") (pintype "tri_state"))
    )
    (net (code "66") (name "unconnected-(IC2-QH'-Pad9)") (class "Default")
      (node (ref "IC2") (pin "9") (pinfunction "QH'_9") (pintype "output"))
    )
    (net (code "67") (name "unconnected-(IC7-Y5-Pad4)") (class "Default")
      (node (ref "IC7") (pin "4") (pinfunction "Y5_4") (pintype "bidirectional"))
    )
    (net (code "68") (name "unconnected-(IC7-Y6-Pad3)") (class "Default")
      (node (ref "IC7") (pin "3") (pinfunction "Y6_3") (pintype "bidirectional"))
    )
    (net (code "69") (name "unconnected-(IC7-Y7-Pad2)") (class "Default")
      (node (ref "IC7") (pin "2") (pinfunction "Y7_2") (pintype "bidirectional"))
    )
    (net (code "70") (name "unconnected-(IC7-Y8-Pad23)") (class "Default")
      (node (ref "IC7") (pin "23") (pinfunction "Y8_23") (pintype "bidirectional"))
    )
    (net (code "71") (name "unconnected-(IC7-Y9-Pad22)") (class "Default")
      (node (ref "IC7") (pin "22") (pinfunction "Y9_22") (pintype "bidirectional"))
    )
    (net (code "72") (name "unconnected-(IC7-Y10-Pad21)") (class "Default")
      (node (ref "IC7") (pin "21") (pinfunction "Y10_21") (pintype "bidirectional"))
    )
    (net (code "73") (name "unconnected-(U2-EN-Pad1)") (class "Default")
      (node (ref "U2") (pin "1") (pinfunction "EN_1") (pintype "input"))
    )
    (net (code "74") (name "unconnected-(U2-GPIO2-Pad19)") (class "Default")
      (node (ref "U2") (pin "19") (pinfunction "GPIO2_19") (pintype "bidirectional"))
    )
    (net (code "75") (name "unconnected-(U2-GPIO4-Pad20)") (class "Default")
      (node (ref "U2") (pin "20") (pinfunction "GPIO4_20") (pintype "bidirectional"))
    )
    (net (code "76") (name "unconnected-(U2-GPIO12-Pad12)") (class "Default")
      (node (ref "U2") (pin "12") (pinfunction "GPIO12_12") (pintype "bidirectional"))
    )
    (net (code "77") (name "unconnected-(U2-GPIO13-Pad13)") (class "Default")
      (node (ref "U2") (pin "13") (pinfunction "GPIO13_13") (pintype "bidirectional"))
    )
    (net (code "78") (name "unconnected-(U2-GPIO14-Pad11)") (class "Default")
      (node (ref "U2") (pin "11") (pinfunction "GPIO14_11") (pintype "bidirectional"))
    )
    (net (code "79") (name "unconnected-(U2-SENSOR_VN-Pad3)") (class "Default")
      (node (ref "U2") (pin "3") (pinfunction "SENSOR_VN_3") (pintype "input"))
    )
    (net (code "80") (name "unconnected-(U2-SENSOR_VP-Pad2)") (class "Default")
      (node (ref "U2") (pin "2") (pinfunction "SENSOR_VP_2") (pintype "input"))
    )
    (net (code "81") (name "unconnected-(U2-UART_0_RX-Pad27)") (class "Default")
      (node (ref "U2") (pin "27") (pinfunction "UART_0_RX_27") (pintype "bidirectional"))
    )
    (net (code "82") (name "unconnected-(U2-UART_0_TX-Pad28)") (class "Default")
      (node (ref "U2") (pin "28") (pinfunction "UART_0_TX_28") (pintype "bidirectional"))
    )
    (net (code "83") (name "unconnected-(U2-UART_2_RX-Pad21)") (class "Default")
      (node (ref "U2") (pin "21") (pinfunction "UART_2_RX_21") (pintype "bidirectional"))
    )
    (net (code "84") (name "unconnected-(U2-UART_2_TX-Pad22)") (class "Default")
      (node (ref "U2") (pin "22") (pinfunction "UART_2_TX_22") (pintype "bidirectional"))
    )
  )
)
